# led.net
KiCad netlist of a schematic drawn in EAGLE
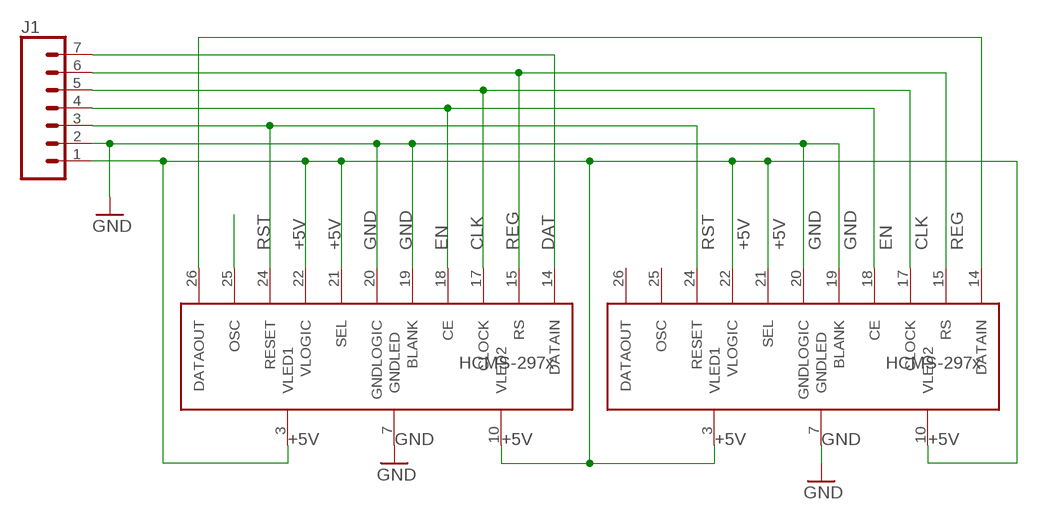
[diagram p0: schematic, sheet 1]

(export (version "E")
  (design (tool "Eeschema 10.0.6"))
  (components
    (comp (ref "J1")
      (value "CONN_07LONGPADS")
      (footprint "eagle-import:1X07_LONGPADS")
      (libsource (lib "eagle-import") (part "CONN_07LONGPADS"))
    )
    (comp (ref "U$1")
      (value "HCMS-297X")
      (footprint "eagle-import:HCMS-297X")
      (libsource (lib "eagle-import") (part "HCMS-297X"))
    )
    (comp (ref "U$2")
      (value "HCMS-297X")
      (footprint "eagle-import:HCMS-297X")
      (libsource (lib "eagle-import") (part "HCMS-297X"))
    )
  )
  (nets
    (net (code "1") (name "/+5V") (class "Default")
      (node (ref "J1") (pin "1") (pinfunction "1_1") (pintype "passive"))
      (node (ref "U$1") (pin "10") (pinfunction "VLED2_10") (pintype "bidirectional"))
      (node (ref "U$1") (pin "21") (pinfunction "SEL_21") (pintype "bidirectional"))
      (node (ref "U$1") (pin "22") (pinfunction "VLOGIC_22") (pintype "bidirectional"))
      (node (ref "U$1") (pin "3") (pinfunction "VLED1_3") (pintype "bidirectional"))
      (node (ref "U$2") (pin "10") (pinfunction "VLED2_10") (pintype "bidirectional"))
      (node (ref "U$2") (pin "21") (pinfunction "SEL_21") (pintype "bidirectional"))
      (node (ref "U$2") (pin "22") (pinfunction "VLOGIC_22") (pintype "bidirectional"))
      (node (ref "U$2") (pin "3") (pinfunction "VLED1_3") (pintype "bidirectional"))
    )
    (net (code "2") (name "/CLK") (class "Default")
      (node (ref "J1") (pin "5") (pinfunction "5_5") (pintype "passive"))
      (node (ref "U$1") (pin "17") (pinfunction "CLOCK_17") (pintype "bidirectional"))
      (node (ref "U$2") (pin "17") (pinfunction "CLOCK_17") (pintype "bidirectional"))
    )
    (net (code "3") (name "/DAT") (class "Default")
      (node (ref "J1") (pin "7") (pinfunction "7_7") (pintype "passive"))
      (node (ref "U$1") (pin "14") (pinfunction "DATAIN_14") (pintype "bidirectional"))
    )
    (net (code "4") (name "/EN") (class "Default")
      (node (ref "J1") (pin "4") (pinfunction "4_4") (pintype "passive"))
      (node (ref "U$1") (pin "18") (pinfunction "CE_18") (pintype "bidirectional"))
      (node (ref "U$2") (pin "18") (pinfunction "CE_18") (pintype "bidirectional"))
    )
    (net (code "5") (name "/REG") (class "Default")
      (node (ref "J1") (pin "6") (pinfunction "6_6") (pintype "passive"))
      (node (ref "U$1") (pin "15") (pinfunction "RS_15") (pintype "bidirectional"))
      (node (ref "U$2") (pin "15") (pinfunction "RS_15") (pintype "bidirectional"))
    )
    (net (code "6") (name "/RST") (class "Default")
      (node (ref "J1") (pin "3") (pinfunction "3_3") (pintype "passive"))
      (node (ref "U$1") (pin "24") (pinfunction "RESET_24") (pintype "bidirectional"))
      (node (ref "U$2") (pin "24") (pinfunction "RESET_24") (pintype "bidirectional"))
    )
    (net (code "7") (name "GND") (class "Default")
      (node (ref "J1") (pin "2") (pinfunction "2_2") (pintype "passive"))
      (node (ref "U$1") (pin "19") (pinfunction "BLANK_19") (pintype "bidirectional"))
      (node (ref "U$1") (pin "20") (pinfunction "GNDLOGIC_20") (pintype "bidirectional"))
      (node (ref "U$1") (pin "7") (pinfunction "GNDLED_7") (pintype "bidirectional"))
      (node (ref "U$2") (pin "19") (pinfunction "BLANK_19") (pintype "bidirectional"))
      (node (ref "U$2") (pin "20") (pinfunction "GNDLOGIC_20") (pintype "bidirectional"))
      (node (ref "U$2") (pin "7") (pinfunction "GNDLED_7") (pintype "bidirectional"))
    )
    (net (code "8") (name "Net-(U$1-DATAOUT)") (class "Default")
      (node (ref "U$1") (pin "26") (pinfunction "DATAOUT_26") (pintype "bidirectional"))
      (node (ref "U$2") (pin "14") (pinfunction "DATAIN_14") (pintype "bidirectional"))
    )
    (net (code "9") (name "unconnected-(U$1-OSC-Pad25)") (class "Default")
      (node (ref "U$1") (pin "25") (pinfunction "OSC_25") (pintype "bidirectional"))
    )
    (net (code "10") (name "unconnected-(U$2-DATAOUT-Pad26)") (class "Default")
      (node (ref "U$2") (pin "26") (pinfunction "DATAOUT_26") (pintype "bidirectional"))
    )
    (net (code "11") (name "unconnected-(U$2-OSC-Pad25)") (class "Default")
      (node (ref "U$2") (pin "25") (pinfunction "OSC_25") (pintype "bidirectional"))
    )
  )
)
